# Adafruit_40pin_TFT_friend.net
KiCad netlist of a schematic drawn in EAGLE
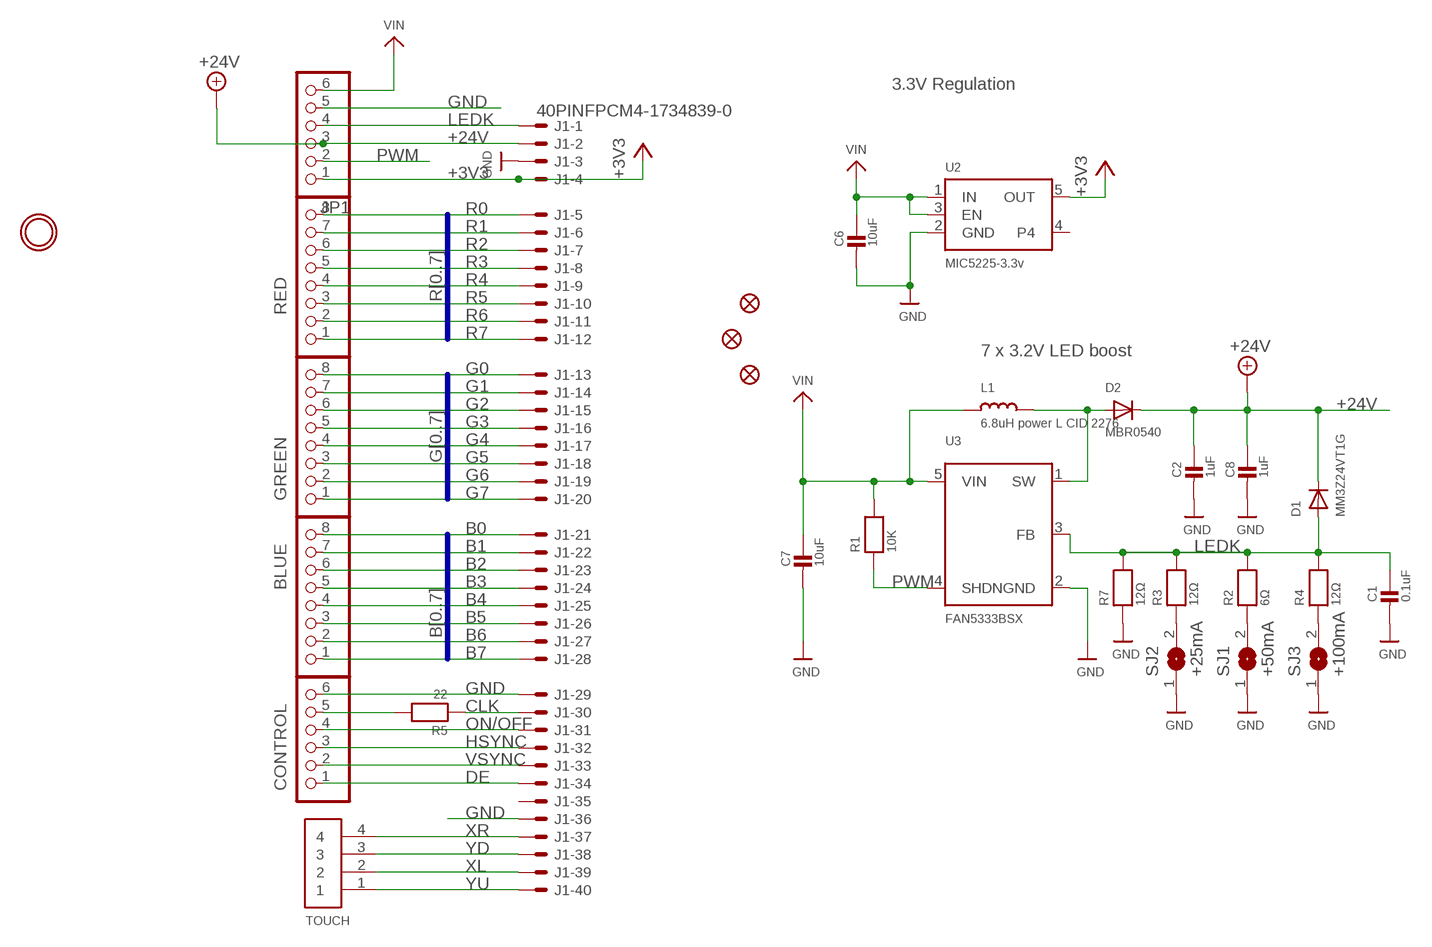
[diagram p0: schematic, sheet 1]

(export (version "E")
  (design (tool "Eeschema 10.0.6"))
  (components
    (comp (ref "BLUE")
      (value "PINHD-1X8BIG")
      (footprint "eagle-import:1X08-BIG")
      (libsource (lib "eagle-import") (part "PINHD-1X8BIG"))
    )
    (comp (ref "C1")
      (value "0.1uF")
      (footprint "eagle-import:_0805MP")
      (libsource (lib "eagle-import") (part "CAP_CERAMIC_0805MP"))
    )
    (comp (ref "C2")
      (value "1uF")
      (footprint "eagle-import:_0805MP")
      (libsource (lib "eagle-import") (part "CAP_CERAMIC_0805MP"))
    )
    (comp (ref "C6")
      (value "10uF")
      (footprint "eagle-import:_0805MP")
      (libsource (lib "eagle-import") (part "CAP_CERAMIC_0805MP"))
    )
    (comp (ref "C7")
      (value "10uF")
      (footprint "eagle-import:_0805MP")
      (libsource (lib "eagle-import") (part "CAP_CERAMIC_0805MP"))
    )
    (comp (ref "C8")
      (value "1uF")
      (footprint "eagle-import:_0805MP")
      (libsource (lib "eagle-import") (part "CAP_CERAMIC_0805MP"))
    )
    (comp (ref "CONTROL")
      (value "PINHD-1X6B")
      (footprint "eagle-import:1X06-BIG")
      (libsource (lib "eagle-import") (part "PINHD-1X6B"))
    )
    (comp (ref "D1")
      (value "MM3Z24VT1G")
      (footprint "eagle-import:SMADIODE")
      (libsource (lib "eagle-import") (part "DIODESMA"))
    )
    (comp (ref "D2")
      (value "MBR0540")
      (footprint "eagle-import:SOD-123")
      (libsource (lib "eagle-import") (part "DIODESOD-123"))
    )
    (comp (ref "FID1")
      (value "FIDUCIAL\"\"")
      (footprint "eagle-import:FIDUCIAL_1MM")
      (libsource (lib "eagle-import") (part "FIDUCIAL{dblquote}{dblquote}"))
    )
    (comp (ref "FID2")
      (value "FIDUCIAL\"\"")
      (footprint "eagle-import:FIDUCIAL_1MM")
      (libsource (lib "eagle-import") (part "FIDUCIAL{dblquote}{dblquote}"))
    )
    (comp (ref "FID3")
      (value "FIDUCIAL\"\"")
      (footprint "eagle-import:FIDUCIAL_1MM")
      (libsource (lib "eagle-import") (part "FIDUCIAL{dblquote}{dblquote}"))
    )
    (comp (ref "GREEN")
      (value "PINHD-1X8BIG")
      (footprint "eagle-import:1X08-BIG")
      (libsource (lib "eagle-import") (part "PINHD-1X8BIG"))
    )
    (comp (ref "J1")
      (value "40PINFPCM4-1734839-0")
      (footprint "eagle-import:4-1734839-0")
      (libsource (lib "eagle-import") (part "40PINFPC4-1734839-0M"))
    )
    (comp (ref "JP1")
      (value "PINHD-1X6B")
      (footprint "eagle-import:1X06-BIG")
      (libsource (lib "eagle-import") (part "PINHD-1X6B"))
    )
    (comp (ref "L1")
      (value "6.8uH power L CID 2276")
      (footprint "eagle-import:INDUCTOR_5X5MM_NR5040_NOTHERMALS")
      (libsource (lib "eagle-import") (part "INDUCTORNR5040"))
    )
    (comp (ref "R1")
      (value "10K")
      (footprint "eagle-import:_0805MP")
      (libsource (lib "eagle-import") (part "RESISTOR_0805MP"))
    )
    (comp (ref "R2")
      (value "6Ω")
      (footprint "eagle-import:_0805MP")
      (libsource (lib "eagle-import") (part "RESISTOR_0805MP"))
    )
    (comp (ref "R3")
      (value "12Ω")
      (footprint "eagle-import:_0805MP")
      (libsource (lib "eagle-import") (part "RESISTOR_0805MP"))
    )
    (comp (ref "R4")
      (value "12Ω")
      (footprint "eagle-import:_0805MP")
      (libsource (lib "eagle-import") (part "RESISTOR_0805MP"))
    )
    (comp (ref "R5")
      (value "22")
      (footprint "eagle-import:_0805MP")
      (libsource (lib "eagle-import") (part "RESISTOR_0805MP"))
    )
    (comp (ref "R7")
      (value "12Ω")
      (footprint "eagle-import:_0805MP")
      (libsource (lib "eagle-import") (part "RESISTOR_0805MP"))
    )
    (comp (ref "RED")
      (value "PINHD-1X8BIG")
      (footprint "eagle-import:1X08-BIG")
      (libsource (lib "eagle-import") (part "PINHD-1X8BIG"))
    )
    (comp (ref "SJ1")
      (value "+50mA")
      (footprint "eagle-import:SOLDERJUMPER_ARROW_NOPASTE")
      (libsource (lib "eagle-import") (part "SOLDERJUMPER"))
    )
    (comp (ref "SJ2")
      (value "+25mA")
      (footprint "eagle-import:SOLDERJUMPER_ARROW_NOPASTE")
      (libsource (lib "eagle-import") (part "SOLDERJUMPER"))
    )
    (comp (ref "SJ3")
      (value "+100mA")
      (footprint "eagle-import:SOLDERJUMPER_ARROW_NOPASTE")
      (libsource (lib "eagle-import") (part "SOLDERJUMPER"))
    )
    (comp (ref "TOUCH")
      (value "1X4-BIG")
      (footprint "eagle-import:1X04-BIG")
      (libsource (lib "eagle-import") (part "1X4-BIG"))
    )
    (comp (ref "U$7")
      (value "MOUNTINGHOLE2.5")
      (footprint "eagle-import:MOUNTINGHOLE_2.5_PLATED")
      (libsource (lib "eagle-import") (part "MOUNTINGHOLE2.5"))
    )
    (comp (ref "U2")
      (value "MIC5225-3.3v")
      (footprint "eagle-import:SOT23-5")
      (libsource (lib "eagle-import") (part "VREG_SOT23-5"))
    )
    (comp (ref "U3")
      (value "FAN5333BSX")
      (footprint "eagle-import:SOT23-5@1")
      (libsource (lib "eagle-import") (part "FAN5331"))
    )
  )
  (nets
    (net (code "1") (name "+3V3") (class "Default")
      (node (ref "J1") (pin "4") (pinfunction "MS_4") (pintype "passive"))
      (node (ref "JP1") (pin "1") (pinfunction "1_1") (pintype "passive"))
      (node (ref "U2") (pin "5") (pinfunction "OUT_5") (pintype "power_in"))
    )
    (net (code "2") (name "+24V") (class "Default")
      (node (ref "C2") (pin "1") (pinfunction "1_1") (pintype "passive"))
      (node (ref "C8") (pin "1") (pinfunction "1_1") (pintype "passive"))
      (node (ref "D1") (pin "C") (pinfunction "C_C") (pintype "passive"))
      (node (ref "D2") (pin "C") (pinfunction "C_C") (pintype "passive"))
      (node (ref "J1") (pin "2") (pinfunction "MS_2") (pintype "passive"))
      (node (ref "JP1") (pin "3") (pinfunction "3_3") (pintype "passive"))
    )
    (net (code "3") (name "/B0") (class "Default")
      (node (ref "BLUE") (pin "8") (pinfunction "8_8") (pintype "passive"))
      (node (ref "J1") (pin "21") (pinfunction "MS_21") (pintype "passive"))
    )
    (net (code "4") (name "/B1") (class "Default")
      (node (ref "BLUE") (pin "7") (pinfunction "7_7") (pintype "passive"))
      (node (ref "J1") (pin "22") (pinfunction "MS_22") (pintype "passive"))
    )
    (net (code "5") (name "/B2") (class "Default")
      (node (ref "BLUE") (pin "6") (pinfunction "6_6") (pintype "passive"))
      (node (ref "J1") (pin "23") (pinfunction "MS_23") (pintype "passive"))
    )
    (net (code "6") (name "/B3") (class "Default")
      (node (ref "BLUE") (pin "5") (pinfunction "5_5") (pintype "passive"))
      (node (ref "J1") (pin "24") (pinfunction "MS_24") (pintype "passive"))
    )
    (net (code "7") (name "/B4") (class "Default")
      (node (ref "BLUE") (pin "4") (pinfunction "4_4") (pintype "passive"))
      (node (ref "J1") (pin "25") (pinfunction "MS_25") (pintype "passive"))
    )
    (net (code "8") (name "/B5") (class "Default")
      (node (ref "BLUE") (pin "3") (pinfunction "3_3") (pintype "passive"))
      (node (ref "J1") (pin "26") (pinfunction "MS_26") (pintype "passive"))
    )
    (net (code "9") (name "/B6") (class "Default")
      (node (ref "BLUE") (pin "2") (pinfunction "2_2") (pintype "passive"))
      (node (ref "J1") (pin "27") (pinfunction "MS_27") (pintype "passive"))
    )
    (net (code "10") (name "/B7") (class "Default")
      (node (ref "BLUE") (pin "1") (pinfunction "1_1") (pintype "passive"))
      (node (ref "J1") (pin "28") (pinfunction "MS_28") (pintype "passive"))
    )
    (net (code "12") (name "/CLK") (class "Default")
      (node (ref "J1") (pin "30") (pinfunction "MS_30") (pintype "passive"))
      (node (ref "R5") (pin "1") (pinfunction "1_1") (pintype "passive"))
    )
    (net (code "13") (name "/DE") (class "Default")
      (node (ref "CONTROL") (pin "1") (pinfunction "1_1") (pintype "passive"))
      (node (ref "J1") (pin "34") (pinfunction "MS_34") (pintype "passive"))
    )
    (net (code "14") (name "/G0") (class "Default")
      (node (ref "GREEN") (pin "8") (pinfunction "8_8") (pintype "passive"))
      (node (ref "J1") (pin "13") (pinfunction "MS_13") (pintype "passive"))
    )
    (net (code "15") (name "/G1") (class "Default")
      (node (ref "GREEN") (pin "7") (pinfunction "7_7") (pintype "passive"))
      (node (ref "J1") (pin "14") (pinfunction "MS_14") (pintype "passive"))
    )
    (net (code "16") (name "/G2") (class "Default")
      (node (ref "GREEN") (pin "6") (pinfunction "6_6") (pintype "passive"))
      (node (ref "J1") (pin "15") (pinfunction "MS_15") (pintype "passive"))
    )
    (net (code "17") (name "/G3") (class "Default")
      (node (ref "GREEN") (pin "5") (pinfunction "5_5") (pintype "passive"))
      (node (ref "J1") (pin "16") (pinfunction "MS_16") (pintype "passive"))
    )
    (net (code "18") (name "/G4") (class "Default")
      (node (ref "GREEN") (pin "4") (pinfunction "4_4") (pintype "passive"))
      (node (ref "J1") (pin "17") (pinfunction "MS_17") (pintype "passive"))
    )
    (net (code "19") (name "/G5") (class "Default")
      (node (ref "GREEN") (pin "3") (pinfunction "3_3") (pintype "passive"))
      (node (ref "J1") (pin "18") (pinfunction "MS_18") (pintype "passive"))
    )
    (net (code "20") (name "/G6") (class "Default")
      (node (ref "GREEN") (pin "2") (pinfunction "2_2") (pintype "passive"))
      (node (ref "J1") (pin "19") (pinfunction "MS_19") (pintype "passive"))
    )
    (net (code "21") (name "/G7") (class "Default")
      (node (ref "GREEN") (pin "1") (pinfunction "1_1") (pintype "passive"))
      (node (ref "J1") (pin "20") (pinfunction "MS_20") (pintype "passive"))
    )
    (net (code "23") (name "/HSYNC") (class "Default")
      (node (ref "CONTROL") (pin "3") (pinfunction "3_3") (pintype "passive"))
      (node (ref "J1") (pin "32") (pinfunction "MS_32") (pintype "passive"))
    )
    (net (code "24") (name "/LEDK") (class "Default")
      (node (ref "C1") (pin "1") (pinfunction "1_1") (pintype "passive"))
      (node (ref "D1") (pin "A") (pinfunction "A_A") (pintype "passive"))
      (node (ref "J1") (pin "1") (pinfunction "MSV_1") (pintype "passive"))
      (node (ref "JP1") (pin "4") (pinfunction "4_4") (pintype "passive"))
      (node (ref "R2") (pin "2") (pinfunction "2_2") (pintype "passive"))
      (node (ref "R3") (pin "2") (pinfunction "2_2") (pintype "passive"))
      (node (ref "R4") (pin "2") (pinfunction "2_2") (pintype "passive"))
      (node (ref "R7") (pin "2") (pinfunction "2_2") (pintype "passive"))
      (node (ref "U3") (pin "3") (pinfunction "FB_3") (pintype "bidirectional"))
    )
    (net (code "25") (name "/ON{slash}OFF") (class "Default")
      (node (ref "CONTROL") (pin "4") (pinfunction "4_4") (pintype "passive"))
      (node (ref "J1") (pin "31") (pinfunction "MS_31") (pintype "passive"))
    )
    (net (code "26") (name "/PWM") (class "Default")
      (node (ref "JP1") (pin "2") (pinfunction "2_2") (pintype "passive"))
      (node (ref "R1") (pin "1") (pinfunction "1_1") (pintype "passive"))
      (node (ref "U3") (pin "4") (pinfunction "SHDN_4") (pintype "bidirectional"))
    )
    (net (code "27") (name "/R0") (class "Default")
      (node (ref "J1") (pin "5") (pinfunction "MS_5") (pintype "passive"))
      (node (ref "RED") (pin "8") (pinfunction "8_8") (pintype "passive"))
    )
    (net (code "28") (name "/R1") (class "Default")
      (node (ref "J1") (pin "6") (pinfunction "MS_6") (pintype "passive"))
      (node (ref "RED") (pin "7") (pinfunction "7_7") (pintype "passive"))
    )
    (net (code "29") (name "/R2") (class "Default")
      (node (ref "J1") (pin "7") (pinfunction "MS_7") (pintype "passive"))
      (node (ref "RED") (pin "6") (pinfunction "6_6") (pintype "passive"))
    )
    (net (code "30") (name "/R3") (class "Default")
      (node (ref "J1") (pin "8") (pinfunction "MS_8") (pintype "passive"))
      (node (ref "RED") (pin "5") (pinfunction "5_5") (pintype "passive"))
    )
    (net (code "31") (name "/R4") (class "Default")
      (node (ref "J1") (pin "9") (pinfunction "MS_9") (pintype "passive"))
      (node (ref "RED") (pin "4") (pinfunction "4_4") (pintype "passive"))
    )
    (net (code "32") (name "/R5") (class "Default")
      (node (ref "J1") (pin "10") (pinfunction "MS_10") (pintype "passive"))
      (node (ref "RED") (pin "3") (pinfunction "3_3") (pintype "passive"))
    )
    (net (code "33") (name "/R6") (class "Default")
      (node (ref "J1") (pin "11") (pinfunction "MS_11") (pintype "passive"))
      (node (ref "RED") (pin "2") (pinfunction "2_2") (pintype "passive"))
    )
    (net (code "34") (name "/R7") (class "Default")
      (node (ref "J1") (pin "12") (pinfunction "MS_12") (pintype "passive"))
      (node (ref "RED") (pin "1") (pinfunction "1_1") (pintype "passive"))
    )
    (net (code "36") (name "/VSYNC") (class "Default")
      (node (ref "CONTROL") (pin "2") (pinfunction "2_2") (pintype "passive"))
      (node (ref "J1") (pin "33") (pinfunction "MS_33") (pintype "passive"))
    )
    (net (code "37") (name "/XL") (class "Default")
      (node (ref "J1") (pin "39") (pinfunction "MS_39") (pintype "passive"))
      (node (ref "TOUCH") (pin "2") (pinfunction "2_2") (pintype "bidirectional"))
    )
    (net (code "38") (name "/XR") (class "Default")
      (node (ref "J1") (pin "37") (pinfunction "MS_37") (pintype "passive"))
      (node (ref "TOUCH") (pin "4") (pinfunction "4_4") (pintype "bidirectional"))
    )
    (net (code "39") (name "/YD") (class "Default")
      (node (ref "J1") (pin "38") (pinfunction "MS_38") (pintype "passive"))
      (node (ref "TOUCH") (pin "3") (pinfunction "3_3") (pintype "bidirectional"))
    )
    (net (code "40") (name "/YU") (class "Default")
      (node (ref "J1") (pin "40") (pinfunction "MS_40") (pintype "passive"))
      (node (ref "TOUCH") (pin "1") (pinfunction "1_1") (pintype "bidirectional"))
    )
    (net (code "41") (name "GND") (class "Default")
      (node (ref "C1") (pin "2") (pinfunction "2_2") (pintype "passive"))
      (node (ref "C2") (pin "2") (pinfunction "2_2") (pintype "passive"))
      (node (ref "C6") (pin "2") (pinfunction "2_2") (pintype "passive"))
      (node (ref "C7") (pin "2") (pinfunction "2_2") (pintype "passive"))
      (node (ref "C8") (pin "2") (pinfunction "2_2") (pintype "passive"))
      (node (ref "CONTROL") (pin "6") (pinfunction "6_6") (pintype "passive"))
      (node (ref "J1") (pin "29") (pinfunction "MS_29") (pintype "passive"))
      (node (ref "J1") (pin "3") (pinfunction "MS_3") (pintype "passive"))
      (node (ref "J1") (pin "36") (pinfunction "MS_36") (pintype "passive"))
      (node (ref "JP1") (pin "5") (pinfunction "5_5") (pintype "passive"))
      (node (ref "R7") (pin "1") (pinfunction "1_1") (pintype "passive"))
      (node (ref "SJ1") (pin "1") (pinfunction "1_1") (pintype "passive"))
      (node (ref "SJ2") (pin "1") (pinfunction "1_1") (pintype "passive"))
      (node (ref "SJ3") (pin "1") (pinfunction "1_1") (pintype "passive"))
      (node (ref "U2") (pin "2") (pinfunction "GND_2") (pintype "power_in"))
      (node (ref "U3") (pin "2") (pinfunction "GND_2") (pintype "bidirectional"))
    )
    (net (code "42") (name "Net-(CONTROL-Pad5)") (class "Default")
      (node (ref "CONTROL") (pin "5") (pinfunction "5_5") (pintype "passive"))
      (node (ref "R5") (pin "2") (pinfunction "2_2") (pintype "passive"))
    )
    (net (code "43") (name "Net-(L1-2)") (class "Default")
      (node (ref "D2") (pin "A") (pinfunction "A_A") (pintype "passive"))
      (node (ref "L1") (pin "P$2") (pinfunction "2_P$2") (pintype "passive"))
      (node (ref "U3") (pin "1") (pinfunction "SW_1") (pintype "bidirectional"))
    )
    (net (code "44") (name "Net-(R2-Pad1)") (class "Default")
      (node (ref "R2") (pin "1") (pinfunction "1_1") (pintype "passive"))
      (node (ref "SJ1") (pin "2") (pinfunction "2_2") (pintype "passive"))
    )
    (net (code "45") (name "Net-(R3-Pad1)") (class "Default")
      (node (ref "R3") (pin "1") (pinfunction "1_1") (pintype "passive"))
      (node (ref "SJ2") (pin "2") (pinfunction "2_2") (pintype "passive"))
    )
    (net (code "46") (name "Net-(R4-Pad1)") (class "Default")
      (node (ref "R4") (pin "1") (pinfunction "1_1") (pintype "passive"))
      (node (ref "SJ3") (pin "2") (pinfunction "2_2") (pintype "passive"))
    )
    (net (code "47") (name "VIN") (class "Default")
      (node (ref "C6") (pin "1") (pinfunction "1_1") (pintype "passive"))
      (node (ref "C7") (pin "1") (pinfunction "1_1") (pintype "passive"))
      (node (ref "JP1") (pin "6") (pinfunction "6_6") (pintype "passive"))
      (node (ref "L1") (pin "P$1") (pinfunction "1_P$1") (pintype "passive"))
      (node (ref "R1") (pin "2") (pinfunction "2_2") (pintype "passive"))
      (node (ref "U2") (pin "1") (pinfunction "IN_1") (pintype "power_in"))
      (node (ref "U2") (pin "3") (pinfunction "EN_3") (pintype "input"))
      (node (ref "U3") (pin "5") (pinfunction "VIN_5") (pintype "bidirectional"))
    )
    (net (code "48") (name "unconnected-(J1AC-MS-Pad35)") (class "Default")
      (node (ref "J1") (pin "35") (pinfunction "MS_35") (pintype "passive"))
    )
    (net (code "49") (name "unconnected-(U2-P4-Pad4)") (class "Default")
      (node (ref "U2") (pin "4") (pinfunction "P4_4") (pintype "bidirectional"))
    )
  )
)
